# voltageRegulator.net
KiCad netlist of a schematic drawn in EAGLE
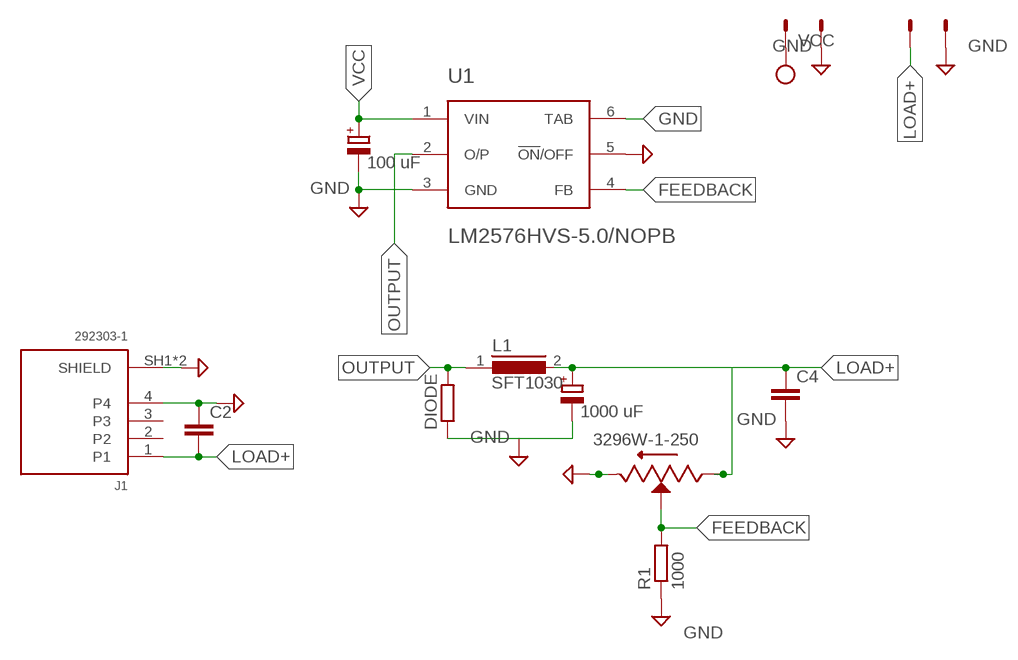
[diagram p0: schematic, sheet 1]

(export (version "E")
  (design (tool "Eeschema 10.0.6"))
  (components
    (comp (ref "C1")
      (value "100 uF")
      (footprint "eagle-import:E5-13")
      (libsource (lib "eagle-import") (part "CPOL-EUE5-13"))
    )
    (comp (ref "C2")
      (value "C-EUC1206K")
      (footprint "eagle-import:C1206K")
      (libsource (lib "eagle-import") (part "C-EUC1206K"))
    )
    (comp (ref "C3")
      (value "1000 uF")
      (footprint "eagle-import:E7,5-16")
      (libsource (lib "eagle-import") (part "CPOL-EUE7.5-16"))
    )
    (comp (ref "C4")
      (value "C-EUC1206K")
      (footprint "eagle-import:C1206K")
      (libsource (lib "eagle-import") (part "C-EUC1206K"))
    )
    (comp (ref "DIODE")
      (value "3000")
      (footprint "eagle-import:R1206")
      (libsource (lib "eagle-import") (part "R-EU_R1206"))
    )
    (comp (ref "INPUT")
      (value "22-23-2021")
      (footprint "eagle-import:22-23-2021")
      (fields (field (name "MF") "MOLEX"))
      (libsource (lib "eagle-import") (part "22-23-2021"))
    )
    (comp (ref "J1")
      (value "292303-1")
      (footprint "eagle-import:TE_292303-1")
      (fields (field (name "MANUFACTURER") "TE Connectivity"))
      (libsource (lib "eagle-import") (part "292303-1"))
    )
    (comp (ref "L1")
      (value "SFT1030")
      (footprint "eagle-import:SFT1030")
      (libsource (lib "eagle-import") (part "SFT1030"))
    )
    (comp (ref "OUTPUT")
      (value "22-23-2021")
      (footprint "eagle-import:22-23-2021")
      (fields (field (name "MF") "MOLEX"))
      (libsource (lib "eagle-import") (part "22-23-2021"))
    )
    (comp (ref "R1")
      (value "1000")
      (footprint "eagle-import:R1206")
      (libsource (lib "eagle-import") (part "R-EU_R1206"))
    )
    (comp (ref "U1")
      (value "LM2576HVS-5.0/NOPB")
      (footprint "eagle-import:DDPAK_TO-263-5")
      (fields
        (field (name "DIGIKEY_PART_NUMBER") "LM2576HVS-5.0/NOPB-ND")
        (field (name "CREATED_BY") "PCBLayout.com")
      )
      (libsource (lib "eagle-import") (part "LM2576HVS-5.0/NOPB"))
    )
    (comp (ref "VR1")
      (value "3296W-1-250")
      (footprint "eagle-import:TRIM_3296W-1-250")
      (fields (field (name "MF") "Bourns"))
      (libsource (lib "eagle-import") (part "3296W-1-250"))
    )
  )
  (nets
    (net (code "1") (name "FEEDBACK") (class "Default")
      (node (ref "R1") (pin "2") (pinfunction "2_2") (pintype "passive"))
      (node (ref "U1") (pin "4") (pinfunction "FB_4") (pintype "input"))
      (node (ref "VR1") (pin "2") (pinfunction "WIPER_2") (pintype "passive"))
    )
    (net (code "2") (name "GND") (class "Default")
      (node (ref "C1") (pin "-") (pinfunction "-_-") (pintype "passive"))
      (node (ref "C2") (pin "1") (pinfunction "1_1") (pintype "passive"))
      (node (ref "C3") (pin "-") (pinfunction "-_-") (pintype "passive"))
      (node (ref "C4") (pin "2") (pinfunction "2_2") (pintype "passive"))
      (node (ref "DIODE") (pin "1") (pinfunction "1_1") (pintype "passive"))
      (node (ref "INPUT") (pin "2") (pinfunction "S_2") (pintype "passive"))
      (node (ref "J1") (pin "4") (pinfunction "P4_4") (pintype "passive"))
      (node (ref "J1") (pin "SH1") (pinfunction "SHIELD_SH1") (pintype "passive"))
      (node (ref "J1") (pin "SH2") (pinfunction "SHIELD_SH2") (pintype "passive"))
      (node (ref "OUTPUT") (pin "2") (pinfunction "S_2") (pintype "passive"))
      (node (ref "R1") (pin "1") (pinfunction "1_1") (pintype "passive"))
      (node (ref "U1") (pin "3") (pinfunction "GND_3") (pintype "power_in"))
      (node (ref "U1") (pin "5") (pinfunction "~{ON}/OFF_5") (pintype "input"))
      (node (ref "U1") (pin "6") (pinfunction "TAB_6") (pintype "power_in"))
      (node (ref "VR1") (pin "3") (pinfunction "CW_3") (pintype "passive"))
    )
    (net (code "3") (name "LOAD+") (class "Default")
      (node (ref "C2") (pin "2") (pinfunction "2_2") (pintype "passive"))
      (node (ref "C3") (pin "+") (pinfunction "+_+") (pintype "passive"))
      (node (ref "C4") (pin "1") (pinfunction "1_1") (pintype "passive"))
      (node (ref "J1") (pin "1") (pinfunction "P1_1") (pintype "passive"))
      (node (ref "L1") (pin "2") (pinfunction "2_2") (pintype "passive"))
      (node (ref "OUTPUT") (pin "1") (pinfunction "S_1") (pintype "passive"))
      (node (ref "VR1") (pin "1") (pinfunction "CCW_1") (pintype "passive"))
    )
    (net (code "4") (name "OUTPUT") (class "Default")
      (node (ref "DIODE") (pin "2") (pinfunction "2_2") (pintype "passive"))
      (node (ref "L1") (pin "1") (pinfunction "1_1") (pintype "passive"))
      (node (ref "U1") (pin "2") (pinfunction "O/P_2") (pintype "output"))
    )
    (net (code "5") (name "VCC") (class "Default")
      (node (ref "C1") (pin "+") (pinfunction "+_+") (pintype "passive"))
      (node (ref "INPUT") (pin "1") (pinfunction "S_1") (pintype "passive"))
      (node (ref "U1") (pin "1") (pinfunction "VIN_1") (pintype "power_in"))
    )
    (net (code "6") (name "unconnected-(J1-P2-Pad2)") (class "Default")
      (node (ref "J1") (pin "2") (pinfunction "P2_2") (pintype "passive"))
    )
    (net (code "7") (name "unconnected-(J1-P3-Pad3)") (class "Default")
      (node (ref "J1") (pin "3") (pinfunction "P3_3") (pintype "passive"))
    )
  )
)
